# connector_to_BMS_extension.net
KiCad netlist of a schematic drawn in Altium Designer
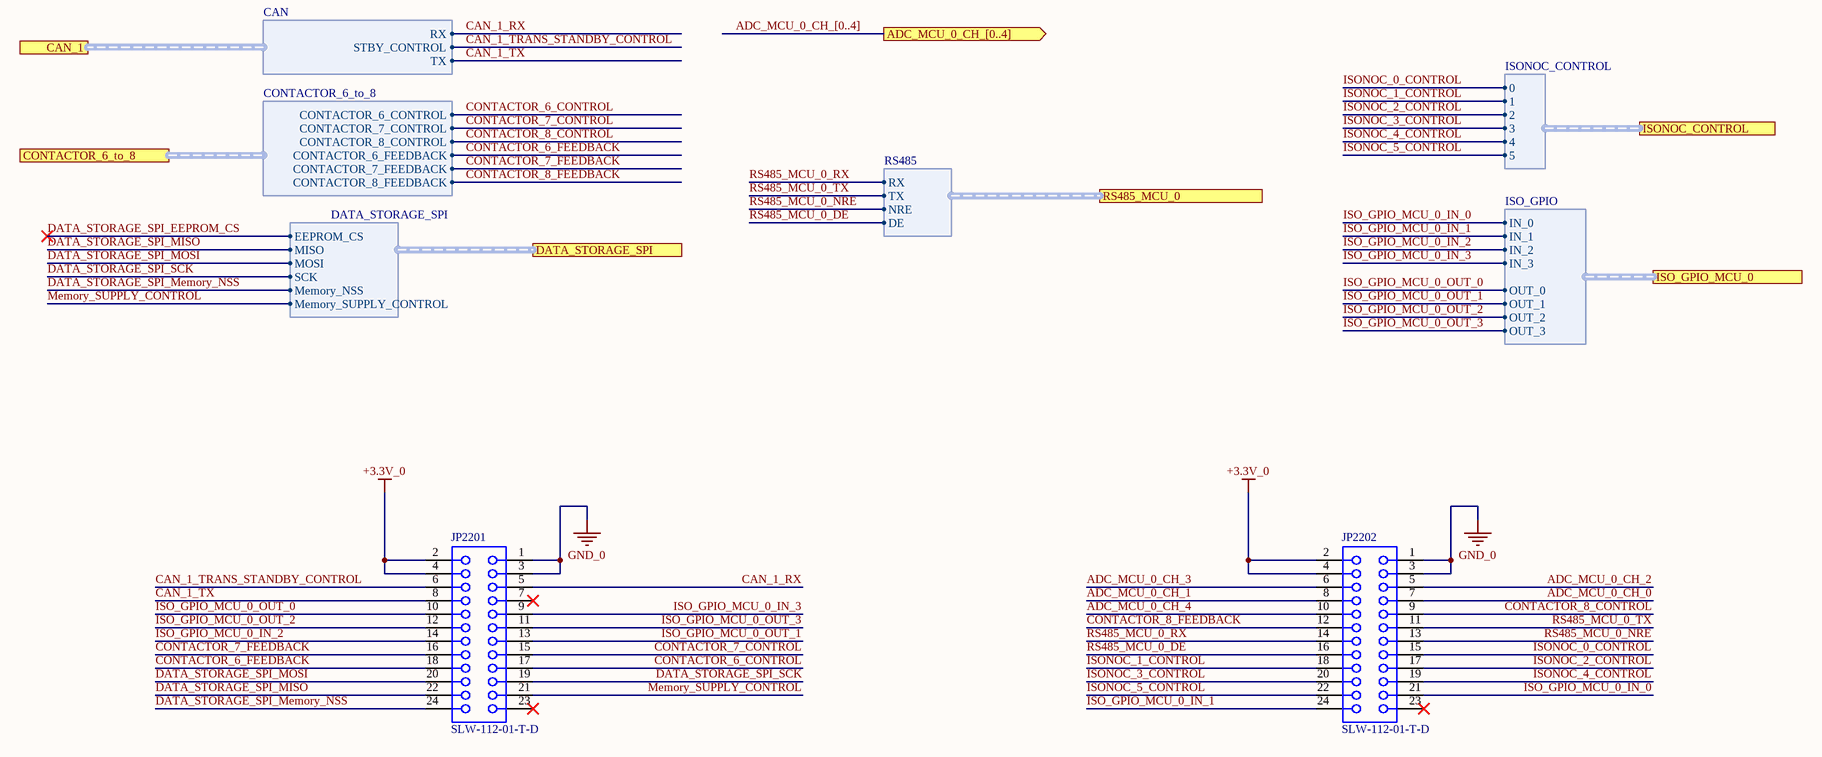
[diagram p0: connector_to_BMS_extension.SchDoc]

(export (version "E")
  (design (tool "Eeschema 10.0.6"))
  (components
    (comp (ref "JP2201")
      (value "SLW-112-01-T-D")
      (footprint "SMTC-SLW-112-01-X-D")
      (fields (field (name "MANUFACTURER") "Samtec"))
      (libsource (lib "Altium Content Vault") (part "SMTC-SLW-112-01-X-D"))
    )
    (comp (ref "JP2202")
      (value "SLW-112-01-T-D")
      (footprint "SMTC-SLW-112-01-X-D")
      (fields (field (name "MANUFACTURER") "Samtec"))
      (libsource (lib "Altium Content Vault") (part "SMTC-SLW-112-01-X-D"))
    )
  )
  (nets
    (net (code "7") (name "+3.3V_0") (class "Default")
      (node (ref "JP2201") (pin "2") (pinfunction "2_2") (pintype "passive"))
      (node (ref "JP2201") (pin "4") (pinfunction "4_4") (pintype "passive"))
      (node (ref "JP2202") (pin "2") (pinfunction "2_2") (pintype "passive"))
      (node (ref "JP2202") (pin "4") (pinfunction "4_4") (pintype "passive"))
    )
    (net (code "8") (name "/ADC_MCU_0_CH_0") (class "Default")
      (node (ref "JP2202") (pin "7") (pinfunction "7_7") (pintype "passive"))
    )
    (net (code "9") (name "/ADC_MCU_0_CH_1") (class "Default")
      (node (ref "JP2202") (pin "8") (pinfunction "8_8") (pintype "passive"))
    )
    (net (code "10") (name "/ADC_MCU_0_CH_2") (class "Default")
      (node (ref "JP2202") (pin "5") (pinfunction "5_5") (pintype "passive"))
    )
    (net (code "11") (name "/ADC_MCU_0_CH_3") (class "Default")
      (node (ref "JP2202") (pin "6") (pinfunction "6_6") (pintype "passive"))
    )
    (net (code "12") (name "/ADC_MCU_0_CH_4") (class "Default")
      (node (ref "JP2202") (pin "10") (pinfunction "10_10") (pintype "passive"))
    )
    (net (code "14") (name "/CAN_1_RX") (class "Default")
      (node (ref "JP2201") (pin "5") (pinfunction "5_5") (pintype "passive"))
    )
    (net (code "15") (name "/CAN_1_TRANS_STANDBY_CONTROL") (class "Default")
      (node (ref "JP2201") (pin "6") (pinfunction "6_6") (pintype "passive"))
    )
    (net (code "16") (name "/CAN_1_TX") (class "Default")
      (node (ref "JP2201") (pin "8") (pinfunction "8_8") (pintype "passive"))
    )
    (net (code "17") (name "/CONTACTOR_6_CONTROL") (class "Default")
      (node (ref "JP2201") (pin "17") (pinfunction "17_17") (pintype "passive"))
    )
    (net (code "18") (name "/CONTACTOR_6_FEEDBACK") (class "Default")
      (node (ref "JP2201") (pin "18") (pinfunction "18_18") (pintype "passive"))
    )
    (net (code "19") (name "/CONTACTOR_7_CONTROL") (class "Default")
      (node (ref "JP2201") (pin "15") (pinfunction "15_15") (pintype "passive"))
    )
    (net (code "20") (name "/CONTACTOR_7_FEEDBACK") (class "Default")
      (node (ref "JP2201") (pin "16") (pinfunction "16_16") (pintype "passive"))
    )
    (net (code "21") (name "/CONTACTOR_8_CONTROL") (class "Default")
      (node (ref "JP2202") (pin "9") (pinfunction "9_9") (pintype "passive"))
    )
    (net (code "22") (name "/CONTACTOR_8_FEEDBACK") (class "Default")
      (node (ref "JP2202") (pin "12") (pinfunction "12_12") (pintype "passive"))
    )
    (net (code "24") (name "/DATA_STORAGE_SPI_MISO") (class "Default")
      (node (ref "JP2201") (pin "22") (pinfunction "22_22") (pintype "passive"))
    )
    (net (code "25") (name "/DATA_STORAGE_SPI_MOSI") (class "Default")
      (node (ref "JP2201") (pin "20") (pinfunction "20_20") (pintype "passive"))
    )
    (net (code "26") (name "/DATA_STORAGE_SPI_Memory_NSS") (class "Default")
      (node (ref "JP2201") (pin "24") (pinfunction "24_24") (pintype "passive"))
    )
    (net (code "27") (name "/DATA_STORAGE_SPI_SCK") (class "Default")
      (node (ref "JP2201") (pin "19") (pinfunction "19_19") (pintype "passive"))
    )
    (net (code "28") (name "/ISONOC_0_CONTROL") (class "Default")
      (node (ref "JP2202") (pin "15") (pinfunction "15_15") (pintype "passive"))
    )
    (net (code "29") (name "/ISONOC_1_CONTROL") (class "Default")
      (node (ref "JP2202") (pin "18") (pinfunction "18_18") (pintype "passive"))
    )
    (net (code "30") (name "/ISONOC_2_CONTROL") (class "Default")
      (node (ref "JP2202") (pin "17") (pinfunction "17_17") (pintype "passive"))
    )
    (net (code "31") (name "/ISONOC_3_CONTROL") (class "Default")
      (node (ref "JP2202") (pin "20") (pinfunction "20_20") (pintype "passive"))
    )
    (net (code "32") (name "/ISONOC_4_CONTROL") (class "Default")
      (node (ref "JP2202") (pin "19") (pinfunction "19_19") (pintype "passive"))
    )
    (net (code "33") (name "/ISONOC_5_CONTROL") (class "Default")
      (node (ref "JP2202") (pin "22") (pinfunction "22_22") (pintype "passive"))
    )
    (net (code "34") (name "/ISO_GPIO_MCU_0_IN_0") (class "Default")
      (node (ref "JP2202") (pin "21") (pinfunction "21_21") (pintype "passive"))
    )
    (net (code "35") (name "/ISO_GPIO_MCU_0_IN_1") (class "Default")
      (node (ref "JP2202") (pin "24") (pinfunction "24_24") (pintype "passive"))
    )
    (net (code "36") (name "/ISO_GPIO_MCU_0_IN_2") (class "Default")
      (node (ref "JP2201") (pin "14") (pinfunction "14_14") (pintype "passive"))
    )
    (net (code "37") (name "/ISO_GPIO_MCU_0_IN_3") (class "Default")
      (node (ref "JP2201") (pin "9") (pinfunction "9_9") (pintype "passive"))
    )
    (net (code "38") (name "/ISO_GPIO_MCU_0_OUT_0") (class "Default")
      (node (ref "JP2201") (pin "10") (pinfunction "10_10") (pintype "passive"))
    )
    (net (code "39") (name "/ISO_GPIO_MCU_0_OUT_1") (class "Default")
      (node (ref "JP2201") (pin "13") (pinfunction "13_13") (pintype "passive"))
    )
    (net (code "40") (name "/ISO_GPIO_MCU_0_OUT_2") (class "Default")
      (node (ref "JP2201") (pin "12") (pinfunction "12_12") (pintype "passive"))
    )
    (net (code "41") (name "/ISO_GPIO_MCU_0_OUT_3") (class "Default")
      (node (ref "JP2201") (pin "11") (pinfunction "11_11") (pintype "passive"))
    )
    (net (code "42") (name "/Memory_SUPPLY_CONTROL") (class "Default")
      (node (ref "JP2201") (pin "21") (pinfunction "21_21") (pintype "passive"))
    )
    (net (code "43") (name "/RS485_MCU_0_DE") (class "Default")
      (node (ref "JP2202") (pin "16") (pinfunction "16_16") (pintype "passive"))
    )
    (net (code "44") (name "/RS485_MCU_0_NRE") (class "Default")
      (node (ref "JP2202") (pin "13") (pinfunction "13_13") (pintype "passive"))
    )
    (net (code "45") (name "/RS485_MCU_0_RX") (class "Default")
      (node (ref "JP2202") (pin "14") (pinfunction "14_14") (pintype "passive"))
    )
    (net (code "46") (name "/RS485_MCU_0_TX") (class "Default")
      (node (ref "JP2202") (pin "11") (pinfunction "11_11") (pintype "passive"))
    )
    (net (code "53") (name "GND_0") (class "Default")
      (node (ref "JP2201") (pin "1") (pinfunction "1_1") (pintype "passive"))
      (node (ref "JP2201") (pin "3") (pinfunction "3_3") (pintype "passive"))
      (node (ref "JP2202") (pin "1") (pinfunction "1_1") (pintype "passive"))
      (node (ref "JP2202") (pin "3") (pinfunction "3_3") (pintype "passive"))
    )
    (net (code "54") (name "unconnected-(JP2201-Pad7)") (class "Default")
      (node (ref "JP2201") (pin "7") (pinfunction "7_7") (pintype "passive+no_connect"))
    )
    (net (code "55") (name "unconnected-(JP2201-Pad23)") (class "Default")
      (node (ref "JP2201") (pin "23") (pinfunction "23_23") (pintype "passive+no_connect"))
    )
    (net (code "56") (name "unconnected-(JP2202-Pad23)") (class "Default")
      (node (ref "JP2202") (pin "23") (pinfunction "23_23") (pintype "passive+no_connect"))
    )
  )
)
